# 02_FPGA_Interface.net
KiCad netlist of a schematic drawn in Altium Designer
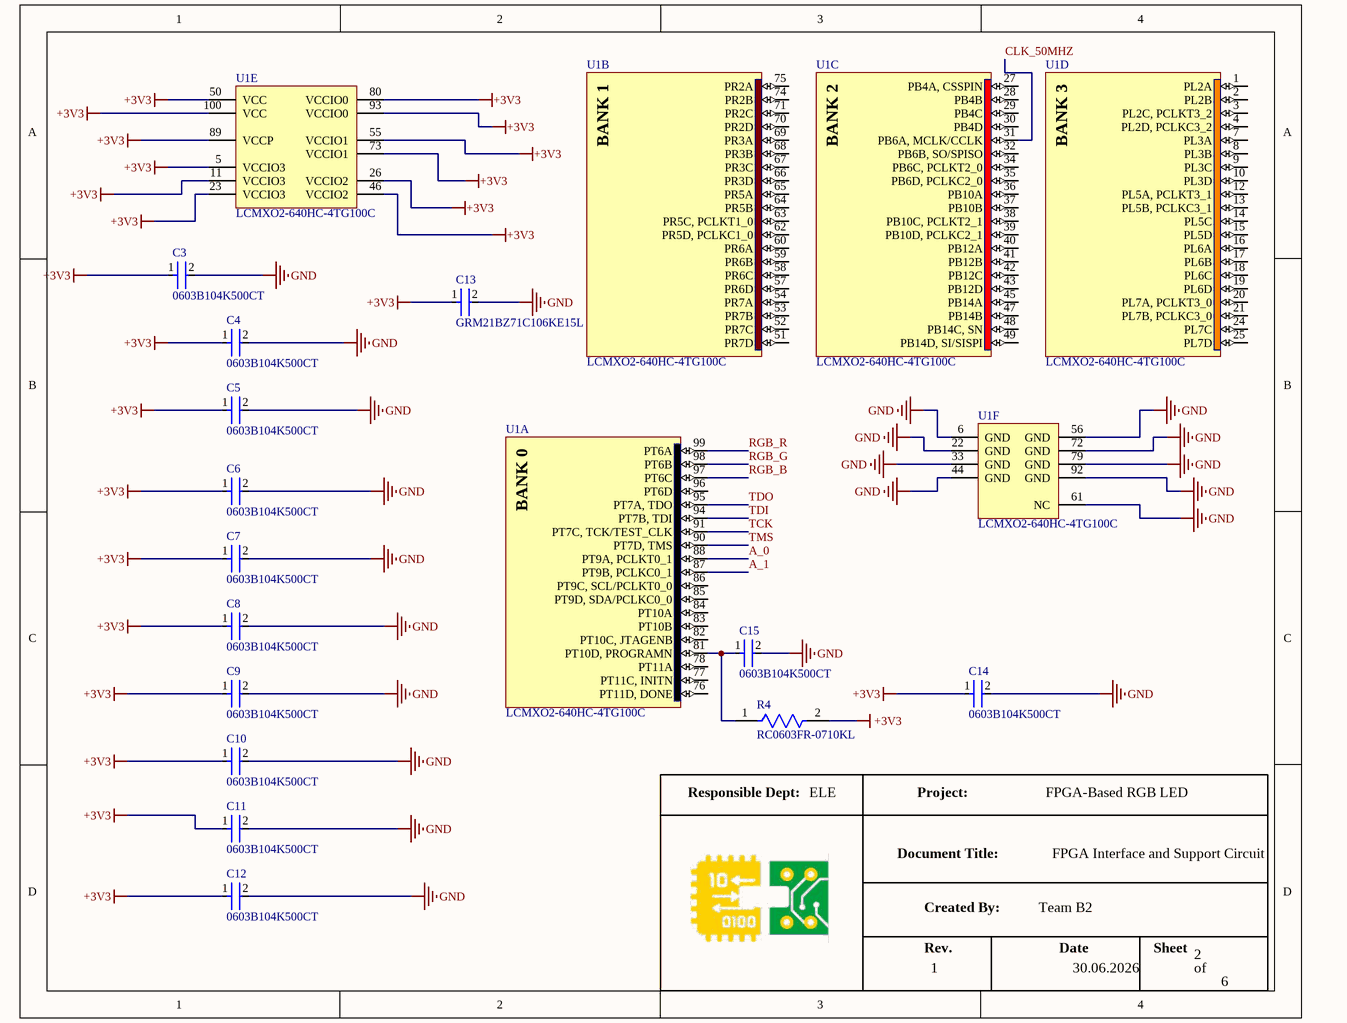
[diagram p0: 02_FPGA_Interface.SchDoc]

(export (version "E")
  (design (tool "Eeschema 10.0.6"))
  (components
    (comp (ref "C3")
      (value "0603B104K500CT")
      (footprint "FP-0603B104K500CT-IPC_C")
      (description "CAP CER 0.1UF 50V X7R 0603")
      (fields (field (name "TOLERANCE") "10%"))
      (libsource (lib "Altium Content Vault") (part "02cd4be3c70576c341d710602a673aa"))
    )
    (comp (ref "C4")
      (value "0603B104K500CT")
      (footprint "FP-0603B104K500CT-IPC_C")
      (description "CAP CER 0.1UF 50V X7R 0603")
      (fields (field (name "TOLERANCE") "10%"))
      (libsource (lib "Altium Content Vault") (part "02cd4be3c70576c341d710602a673aa"))
    )
    (comp (ref "C5")
      (value "0603B104K500CT")
      (footprint "FP-0603B104K500CT-IPC_C")
      (description "CAP CER 0.1UF 50V X7R 0603")
      (fields (field (name "TOLERANCE") "10%"))
      (libsource (lib "Altium Content Vault") (part "02cd4be3c70576c341d710602a673aa"))
    )
    (comp (ref "C6")
      (value "0603B104K500CT")
      (footprint "FP-0603B104K500CT-IPC_C")
      (description "CAP CER 0.1UF 50V X7R 0603")
      (fields (field (name "TOLERANCE") "10%"))
      (libsource (lib "Altium Content Vault") (part "02cd4be3c70576c341d710602a673aa"))
    )
    (comp (ref "C7")
      (value "0603B104K500CT")
      (footprint "FP-0603B104K500CT-IPC_C")
      (description "CAP CER 0.1UF 50V X7R 0603")
      (fields (field (name "TOLERANCE") "10%"))
      (libsource (lib "Altium Content Vault") (part "02cd4be3c70576c341d710602a673aa"))
    )
    (comp (ref "C8")
      (value "0603B104K500CT")
      (footprint "FP-0603B104K500CT-IPC_C")
      (description "CAP CER 0.1UF 50V X7R 0603")
      (fields (field (name "TOLERANCE") "10%"))
      (libsource (lib "Altium Content Vault") (part "02cd4be3c70576c341d710602a673aa"))
    )
    (comp (ref "C9")
      (value "0603B104K500CT")
      (footprint "FP-0603B104K500CT-IPC_C")
      (description "CAP CER 0.1UF 50V X7R 0603")
      (fields (field (name "TOLERANCE") "10%"))
      (libsource (lib "Altium Content Vault") (part "02cd4be3c70576c341d710602a673aa"))
    )
    (comp (ref "C10")
      (value "0603B104K500CT")
      (footprint "FP-0603B104K500CT-IPC_C")
      (description "CAP CER 0.1UF 50V X7R 0603")
      (fields (field (name "TOLERANCE") "10%"))
      (libsource (lib "Altium Content Vault") (part "02cd4be3c70576c341d710602a673aa"))
    )
    (comp (ref "C11")
      (value "0603B104K500CT")
      (footprint "FP-0603B104K500CT-IPC_C")
      (description "CAP CER 0.1UF 50V X7R 0603")
      (fields (field (name "TOLERANCE") "10%"))
      (libsource (lib "Altium Content Vault") (part "02cd4be3c70576c341d710602a673aa"))
    )
    (comp (ref "C12")
      (value "0603B104K500CT")
      (footprint "FP-0603B104K500CT-IPC_C")
      (description "CAP CER 0.1UF 50V X7R 0603")
      (fields (field (name "TOLERANCE") "10%"))
      (libsource (lib "Altium Content Vault") (part "02cd4be3c70576c341d710602a673aa"))
    )
    (comp (ref "C13")
      (value "GRM21BZ71C106KE15L")
      (footprint "FP-GRM21B-0_2-e0_2_0_7-IPC_C")
      (description "Chip Multilayer Ceramic Capacitors for General Purpose, 0805, 10uF, X7R, 15%, 10%, 16V")
      (libsource (lib "Altium Content Vault") (part "b4654b650e69147ec39a6b967a45e02"))
    )
    (comp (ref "C14")
      (value "0603B104K500CT")
      (footprint "FP-0603B104K500CT-IPC_C")
      (description "CAP CER 0.1UF 50V X7R 0603")
      (fields (field (name "TOLERANCE") "10%"))
      (libsource (lib "Altium Content Vault") (part "02cd4be3c70576c341d710602a673aa"))
    )
    (comp (ref "C15")
      (value "0603B104K500CT")
      (footprint "FP-0603B104K500CT-IPC_C")
      (description "CAP CER 0.1UF 50V X7R 0603")
      (fields (field (name "TOLERANCE") "10%"))
      (libsource (lib "Altium Content Vault") (part "02cd4be3c70576c341d710602a673aa"))
    )
    (comp (ref "R4")
      (value "RC0603FR-0710KL")
      (footprint "FP-RC0603-0_55-IPC_C")
      (description "RES 10K OHM 1% 1/10W 0603")
      (fields (field (name "TOLERANCE") "1%"))
      (libsource (lib "Altium Content Vault") (part "1029c3af85768c4190bb7ad29bc67b5"))
    )
    (comp (ref "U1")
      (value "LCMXO2-640HC-4TG100C")
      (footprint "TQFP100_M")
      (libsource (lib "Altium Content Vault") (part "PLD-LTMXO2-640-TQ100"))
    )
  )
  (nets
    (net (code "1") (name "+3V3") (class "Default")
      (node (ref "C10") (pin "1") (pinfunction "1_1") (pintype "passive"))
      (node (ref "C11") (pin "1") (pinfunction "1_1") (pintype "passive"))
      (node (ref "C12") (pin "1") (pinfunction "1_1") (pintype "passive"))
      (node (ref "C13") (pin "1") (pinfunction "1_1") (pintype "passive"))
      (node (ref "C14") (pin "1") (pinfunction "1_1") (pintype "passive"))
      (node (ref "C3") (pin "1") (pinfunction "1_1") (pintype "passive"))
      (node (ref "C4") (pin "1") (pinfunction "1_1") (pintype "passive"))
      (node (ref "C5") (pin "1") (pinfunction "1_1") (pintype "passive"))
      (node (ref "C6") (pin "1") (pinfunction "1_1") (pintype "passive"))
      (node (ref "C7") (pin "1") (pinfunction "1_1") (pintype "passive"))
      (node (ref "C8") (pin "1") (pinfunction "1_1") (pintype "passive"))
      (node (ref "C9") (pin "1") (pinfunction "1_1") (pintype "passive"))
      (node (ref "R4") (pin "2") (pinfunction "2_2") (pintype "passive"))
      (node (ref "U1") (pin "100") (pinfunction "VCC_100") (pintype "power_in"))
      (node (ref "U1") (pin "11") (pinfunction "VCCIO3_11") (pintype "power_in"))
      (node (ref "U1") (pin "23") (pinfunction "VCCIO3_23") (pintype "power_in"))
      (node (ref "U1") (pin "26") (pinfunction "VCCIO2_26") (pintype "power_in"))
      (node (ref "U1") (pin "46") (pinfunction "VCCIO2_46") (pintype "power_in"))
      (node (ref "U1") (pin "5") (pinfunction "VCCIO3_5") (pintype "power_in"))
      (node (ref "U1") (pin "50") (pinfunction "VCC_50") (pintype "power_in"))
      (node (ref "U1") (pin "55") (pinfunction "VCCIO1_55") (pintype "power_in"))
      (node (ref "U1") (pin "73") (pinfunction "VCCIO1_73") (pintype "power_in"))
      (node (ref "U1") (pin "80") (pinfunction "VCCIO0_80") (pintype "power_in"))
      (node (ref "U1") (pin "89") (pinfunction "VCCP_89") (pintype "power_in"))
      (node (ref "U1") (pin "93") (pinfunction "VCCIO0_93") (pintype "power_in"))
    )
    (net (code "2") (name "/A_0") (class "Default")
      (node (ref "U1") (pin "88") (pinfunction "PT9A,_PCLKT0_1_88") (pintype "bidirectional"))
    )
    (net (code "3") (name "/A_1") (class "Default")
      (node (ref "U1") (pin "87") (pinfunction "PT9B,_PCLKC0_1_87") (pintype "bidirectional"))
    )
    (net (code "4") (name "/CLK_50MHZ") (class "Default")
      (node (ref "U1") (pin "31") (pinfunction "PB6A,_MCLK/CCLK_31") (pintype "bidirectional"))
    )
    (net (code "5") (name "/RGB_B") (class "Default")
      (node (ref "U1") (pin "97") (pinfunction "PT6C_97") (pintype "bidirectional"))
    )
    (net (code "6") (name "/RGB_G") (class "Default")
      (node (ref "U1") (pin "98") (pinfunction "PT6B_98") (pintype "bidirectional"))
    )
    (net (code "7") (name "/RGB_R") (class "Default")
      (node (ref "U1") (pin "99") (pinfunction "PT6A_99") (pintype "bidirectional"))
    )
    (net (code "8") (name "/TCK") (class "Default")
      (node (ref "U1") (pin "91") (pinfunction "PT7C,_TCK/TEST_CLK_91") (pintype "bidirectional"))
    )
    (net (code "9") (name "/TDI") (class "Default")
      (node (ref "U1") (pin "94") (pinfunction "PT7B,_TDI_94") (pintype "bidirectional"))
    )
    (net (code "10") (name "/TDO") (class "Default")
      (node (ref "U1") (pin "95") (pinfunction "PT7A,_TDO_95") (pintype "bidirectional"))
    )
    (net (code "11") (name "/TMS") (class "Default")
      (node (ref "U1") (pin "90") (pinfunction "PT7D,_TMS_90") (pintype "bidirectional"))
    )
    (net (code "12") (name "GND") (class "Default")
      (node (ref "C10") (pin "2") (pinfunction "2_2") (pintype "passive"))
      (node (ref "C11") (pin "2") (pinfunction "2_2") (pintype "passive"))
      (node (ref "C12") (pin "2") (pinfunction "2_2") (pintype "passive"))
      (node (ref "C13") (pin "2") (pinfunction "2_2") (pintype "passive"))
      (node (ref "C14") (pin "2") (pinfunction "2_2") (pintype "passive"))
      (node (ref "C15") (pin "2") (pinfunction "2_2") (pintype "passive"))
      (node (ref "C3") (pin "2") (pinfunction "2_2") (pintype "passive"))
      (node (ref "C4") (pin "2") (pinfunction "2_2") (pintype "passive"))
      (node (ref "C5") (pin "2") (pinfunction "2_2") (pintype "passive"))
      (node (ref "C6") (pin "2") (pinfunction "2_2") (pintype "passive"))
      (node (ref "C7") (pin "2") (pinfunction "2_2") (pintype "passive"))
      (node (ref "C8") (pin "2") (pinfunction "2_2") (pintype "passive"))
      (node (ref "C9") (pin "2") (pinfunction "2_2") (pintype "passive"))
      (node (ref "U1") (pin "22") (pinfunction "GND_22") (pintype "power_in"))
      (node (ref "U1") (pin "33") (pinfunction "GND_33") (pintype "power_in"))
      (node (ref "U1") (pin "44") (pinfunction "GND_44") (pintype "power_in"))
      (node (ref "U1") (pin "56") (pinfunction "GND_56") (pintype "power_in"))
      (node (ref "U1") (pin "6") (pinfunction "GND_6") (pintype "power_in"))
      (node (ref "U1") (pin "61") (pinfunction "NC_61") (pintype "passive"))
      (node (ref "U1") (pin "72") (pinfunction "GND_72") (pintype "power_in"))
      (node (ref "U1") (pin "79") (pinfunction "GND_79") (pintype "power_in"))
      (node (ref "U1") (pin "92") (pinfunction "GND_92") (pintype "power_in"))
    )
    (net (code "13") (name "Net-(U1A-PT10D,_PROGRAMN)") (class "Default")
      (node (ref "C15") (pin "1") (pinfunction "1_1") (pintype "passive"))
      (node (ref "R4") (pin "1") (pinfunction "1_1") (pintype "passive"))
      (node (ref "U1") (pin "81") (pinfunction "PT10D,_PROGRAMN_81") (pintype "bidirectional"))
    )
    (net (code "14") (name "unconnected-(U1A-PT6D-Pad96)") (class "Default")
      (node (ref "U1") (pin "96") (pinfunction "PT6D_96") (pintype "bidirectional"))
    )
    (net (code "15") (name "unconnected-(U1A-PT9C,_SCL{slash}PCLKT0_0-Pad86)") (class "Default")
      (node (ref "U1") (pin "86") (pinfunction "PT9C,_SCL/PCLKT0_0_86") (pintype "bidirectional"))
    )
    (net (code "16") (name "unconnected-(U1A-PT9D,_SDA{slash}PCLKC0_0-Pad85)") (class "Default")
      (node (ref "U1") (pin "85") (pinfunction "PT9D,_SDA/PCLKC0_0_85") (pintype "bidirectional"))
    )
    (net (code "17") (name "unconnected-(U1A-PT10A-Pad84)") (class "Default")
      (node (ref "U1") (pin "84") (pinfunction "PT10A_84") (pintype "bidirectional"))
    )
    (net (code "18") (name "unconnected-(U1A-PT10B-Pad83)") (class "Default")
      (node (ref "U1") (pin "83") (pinfunction "PT10B_83") (pintype "bidirectional"))
    )
    (net (code "19") (name "unconnected-(U1A-PT10C,_JTAGENB-Pad82)") (class "Default")
      (node (ref "U1") (pin "82") (pinfunction "PT10C,_JTAGENB_82") (pintype "bidirectional"))
    )
    (net (code "20") (name "unconnected-(U1A-PT11A-Pad78)") (class "Default")
      (node (ref "U1") (pin "78") (pinfunction "PT11A_78") (pintype "bidirectional"))
    )
    (net (code "21") (name "unconnected-(U1A-PT11C,_INITN-Pad77)") (class "Default")
      (node (ref "U1") (pin "77") (pinfunction "PT11C,_INITN_77") (pintype "bidirectional"))
    )
    (net (code "22") (name "unconnected-(U1A-PT11D,_DONE-Pad76)") (class "Default")
      (node (ref "U1") (pin "76") (pinfunction "PT11D,_DONE_76") (pintype "bidirectional"))
    )
    (net (code "23") (name "unconnected-(U1B-PR2A-Pad75)") (class "Default")
      (node (ref "U1") (pin "75") (pinfunction "PR2A_75") (pintype "bidirectional"))
    )
    (net (code "24") (name "unconnected-(U1B-PR2B-Pad74)") (class "Default")
      (node (ref "U1") (pin "74") (pinfunction "PR2B_74") (pintype "bidirectional"))
    )
    (net (code "25") (name "unconnected-(U1B-PR2C-Pad71)") (class "Default")
      (node (ref "U1") (pin "71") (pinfunction "PR2C_71") (pintype "bidirectional"))
    )
    (net (code "26") (name "unconnected-(U1B-PR2D-Pad70)") (class "Default")
      (node (ref "U1") (pin "70") (pinfunction "PR2D_70") (pintype "bidirectional"))
    )
    (net (code "27") (name "unconnected-(U1B-PR3A-Pad69)") (class "Default")
      (node (ref "U1") (pin "69") (pinfunction "PR3A_69") (pintype "bidirectional"))
    )
    (net (code "28") (name "unconnected-(U1B-PR3B-Pad68)") (class "Default")
      (node (ref "U1") (pin "68") (pinfunction "PR3B_68") (pintype "bidirectional"))
    )
    (net (code "29") (name "unconnected-(U1B-PR3C-Pad67)") (class "Default")
      (node (ref "U1") (pin "67") (pinfunction "PR3C_67") (pintype "bidirectional"))
    )
    (net (code "30") (name "unconnected-(U1B-PR3D-Pad66)") (class "Default")
      (node (ref "U1") (pin "66") (pinfunction "PR3D_66") (pintype "bidirectional"))
    )
    (net (code "31") (name "unconnected-(U1B-PR5A-Pad65)") (class "Default")
      (node (ref "U1") (pin "65") (pinfunction "PR5A_65") (pintype "bidirectional"))
    )
    (net (code "32") (name "unconnected-(U1B-PR5B-Pad64)") (class "Default")
      (node (ref "U1") (pin "64") (pinfunction "PR5B_64") (pintype "bidirectional"))
    )
    (net (code "33") (name "unconnected-(U1B-PR5C,_PCLKT1_0-Pad63)") (class "Default")
      (node (ref "U1") (pin "63") (pinfunction "PR5C,_PCLKT1_0_63") (pintype "bidirectional"))
    )
    (net (code "34") (name "unconnected-(U1B-PR5D,_PCLKC1_0-Pad62)") (class "Default")
      (node (ref "U1") (pin "62") (pinfunction "PR5D,_PCLKC1_0_62") (pintype "bidirectional"))
    )
    (net (code "35") (name "unconnected-(U1B-PR6A-Pad60)") (class "Default")
      (node (ref "U1") (pin "60") (pinfunction "PR6A_60") (pintype "bidirectional"))
    )
    (net (code "36") (name "unconnected-(U1B-PR6B-Pad59)") (class "Default")
      (node (ref "U1") (pin "59") (pinfunction "PR6B_59") (pintype "bidirectional"))
    )
    (net (code "37") (name "unconnected-(U1B-PR6C-Pad58)") (class "Default")
      (node (ref "U1") (pin "58") (pinfunction "PR6C_58") (pintype "bidirectional"))
    )
    (net (code "38") (name "unconnected-(U1B-PR6D-Pad57)") (class "Default")
      (node (ref "U1") (pin "57") (pinfunction "PR6D_57") (pintype "bidirectional"))
    )
    (net (code "39") (name "unconnected-(U1B-PR7A-Pad54)") (class "Default")
      (node (ref "U1") (pin "54") (pinfunction "PR7A_54") (pintype "bidirectional"))
    )
    (net (code "40") (name "unconnected-(U1B-PR7B-Pad53)") (class "Default")
      (node (ref "U1") (pin "53") (pinfunction "PR7B_53") (pintype "bidirectional"))
    )
    (net (code "41") (name "unconnected-(U1B-PR7C-Pad52)") (class "Default")
      (node (ref "U1") (pin "52") (pinfunction "PR7C_52") (pintype "bidirectional"))
    )
    (net (code "42") (name "unconnected-(U1B-PR7D-Pad51)") (class "Default")
      (node (ref "U1") (pin "51") (pinfunction "PR7D_51") (pintype "bidirectional"))
    )
    (net (code "43") (name "unconnected-(U1C-PB4A,_CSSPIN-Pad27)") (class "Default")
      (node (ref "U1") (pin "27") (pinfunction "PB4A,_CSSPIN_27") (pintype "bidirectional"))
    )
    (net (code "44") (name "unconnected-(U1C-PB4B-Pad28)") (class "Default")
      (node (ref "U1") (pin "28") (pinfunction "PB4B_28") (pintype "bidirectional"))
    )
    (net (code "45") (name "unconnected-(U1C-PB4C-Pad29)") (class "Default")
      (node (ref "U1") (pin "29") (pinfunction "PB4C_29") (pintype "bidirectional"))
    )
    (net (code "46") (name "unconnected-(U1C-PB4D-Pad30)") (class "Default")
      (node (ref "U1") (pin "30") (pinfunction "PB4D_30") (pintype "bidirectional"))
    )
    (net (code "47") (name "unconnected-(U1C-PB6B,_SO{slash}SPISO-Pad32)") (class "Default")
      (node (ref "U1") (pin "32") (pinfunction "PB6B,_SO/SPISO_32") (pintype "bidirectional"))
    )
    (net (code "48") (name "unconnected-(U1C-PB6C,_PCLKT2_0-Pad34)") (class "Default")
      (node (ref "U1") (pin "34") (pinfunction "PB6C,_PCLKT2_0_34") (pintype "bidirectional"))
    )
    (net (code "49") (name "unconnected-(U1C-PB6D,_PCLKC2_0-Pad35)") (class "Default")
      (node (ref "U1") (pin "35") (pinfunction "PB6D,_PCLKC2_0_35") (pintype "bidirectional"))
    )
    (net (code "50") (name "unconnected-(U1C-PB10A-Pad36)") (class "Default")
      (node (ref "U1") (pin "36") (pinfunction "PB10A_36") (pintype "bidirectional"))
    )
    (net (code "51") (name "unconnected-(U1C-PB10B-Pad37)") (class "Default")
      (node (ref "U1") (pin "37") (pinfunction "PB10B_37") (pintype "bidirectional"))
    )
    (net (code "52") (name "unconnected-(U1C-PB10C,_PCLKT2_1-Pad38)") (class "Default")
      (node (ref "U1") (pin "38") (pinfunction "PB10C,_PCLKT2_1_38") (pintype "bidirectional"))
    )
    (net (code "53") (name "unconnected-(U1C-PB10D,_PCLKC2_1-Pad39)") (class "Default")
      (node (ref "U1") (pin "39") (pinfunction "PB10D,_PCLKC2_1_39") (pintype "bidirectional"))
    )
    (net (code "54") (name "unconnected-(U1C-PB12A-Pad40)") (class "Default")
      (node (ref "U1") (pin "40") (pinfunction "PB12A_40") (pintype "bidirectional"))
    )
    (net (code "55") (name "unconnected-(U1C-PB12B-Pad41)") (class "Default")
      (node (ref "U1") (pin "41") (pinfunction "PB12B_41") (pintype "bidirectional"))
    )
    (net (code "56") (name "unconnected-(U1C-PB12C-Pad42)") (class "Default")
      (node (ref "U1") (pin "42") (pinfunction "PB12C_42") (pintype "bidirectional"))
    )
    (net (code "57") (name "unconnected-(U1C-PB12D-Pad43)") (class "Default")
      (node (ref "U1") (pin "43") (pinfunction "PB12D_43") (pintype "bidirectional"))
    )
    (net (code "58") (name "unconnected-(U1C-PB14A-Pad45)") (class "Default")
      (node (ref "U1") (pin "45") (pinfunction "PB14A_45") (pintype "bidirectional"))
    )
    (net (code "59") (name "unconnected-(U1C-PB14B-Pad47)") (class "Default")
      (node (ref "U1") (pin "47") (pinfunction "PB14B_47") (pintype "bidirectional"))
    )
    (net (code "60") (name "unconnected-(U1C-PB14C,_SN-Pad48)") (class "Default")
      (node (ref "U1") (pin "48") (pinfunction "PB14C,_SN_48") (pintype "bidirectional"))
    )
    (net (code "61") (name "unconnected-(U1C-PB14D,_SI{slash}SISPI-Pad49)") (class "Default")
      (node (ref "U1") (pin "49") (pinfunction "PB14D,_SI/SISPI_49") (pintype "bidirectional"))
    )
    (net (code "62") (name "unconnected-(U1D-PL2A-Pad1)") (class "Default")
      (node (ref "U1") (pin "1") (pinfunction "PL2A_1") (pintype "bidirectional"))
    )
    (net (code "63") (name "unconnected-(U1D-PL2B-Pad2)") (class "Default")
      (node (ref "U1") (pin "2") (pinfunction "PL2B_2") (pintype "bidirectional"))
    )
    (net (code "64") (name "unconnected-(U1D-PL2C,_PCLKT3_2-Pad3)") (class "Default")
      (node (ref "U1") (pin "3") (pinfunction "PL2C,_PCLKT3_2_3") (pintype "bidirectional"))
    )
    (net (code "65") (name "unconnected-(U1D-PL2D,_PCLKC3_2-Pad4)") (class "Default")
      (node (ref "U1") (pin "4") (pinfunction "PL2D,_PCLKC3_2_4") (pintype "bidirectional"))
    )
    (net (code "66") (name "unconnected-(U1D-PL3A-Pad7)") (class "Default")
      (node (ref "U1") (pin "7") (pinfunction "PL3A_7") (pintype "bidirectional"))
    )
    (net (code "67") (name "unconnected-(U1D-PL3B-Pad8)") (class "Default")
      (node (ref "U1") (pin "8") (pinfunction "PL3B_8") (pintype "bidirectional"))
    )
    (net (code "68") (name "unconnected-(U1D-PL3C-Pad9)") (class "Default")
      (node (ref "U1") (pin "9") (pinfunction "PL3C_9") (pintype "bidirectional"))
    )
    (net (code "69") (name "unconnected-(U1D-PL3D-Pad10)") (class "Default")
      (node (ref "U1") (pin "10") (pinfunction "PL3D_10") (pintype "bidirectional"))
    )
    (net (code "70") (name "unconnected-(U1D-PL5A,_PCLKT3_1-Pad12)") (class "Default")
      (node (ref "U1") (pin "12") (pinfunction "PL5A,_PCLKT3_1_12") (pintype "bidirectional"))
    )
    (net (code "71") (name "unconnected-(U1D-PL5B,_PCLKC3_1-Pad13)") (class "Default")
      (node (ref "U1") (pin "13") (pinfunction "PL5B,_PCLKC3_1_13") (pintype "bidirectional"))
    )
    (net (code "72") (name "unconnected-(U1D-PL5C-Pad14)") (class "Default")
      (node (ref "U1") (pin "14") (pinfunction "PL5C_14") (pintype "bidirectional"))
    )
    (net (code "73") (name "unconnected-(U1D-PL5D-Pad15)") (class "Default")
      (node (ref "U1") (pin "15") (pinfunction "PL5D_15") (pintype "bidirectional"))
    )
    (net (code "74") (name "unconnected-(U1D-PL6A-Pad16)") (class "Default")
      (node (ref "U1") (pin "16") (pinfunction "PL6A_16") (pintype "bidirectional"))
    )
    (net (code "75") (name "unconnected-(U1D-PL6B-Pad17)") (class "Default")
      (node (ref "U1") (pin "17") (pinfunction "PL6B_17") (pintype "bidirectional"))
    )
    (net (code "76") (name "unconnected-(U1D-PL6C-Pad18)") (class "Default")
      (node (ref "U1") (pin "18") (pinfunction "PL6C_18") (pintype "bidirectional"))
    )
    (net (code "77") (name "unconnected-(U1D-PL6D-Pad19)") (class "Default")
      (node (ref "U1") (pin "19") (pinfunction "PL6D_19") (pintype "bidirectional"))
    )
    (net (code "78") (name "unconnected-(U1D-PL7A,_PCLKT3_0-Pad20)") (class "Default")
      (node (ref "U1") (pin "20") (pinfunction "PL7A,_PCLKT3_0_20") (pintype "bidirectional"))
    )
    (net (code "79") (name "unconnected-(U1D-PL7B,_PCLKC3_0-Pad21)") (class "Default")
      (node (ref "U1") (pin "21") (pinfunction "PL7B,_PCLKC3_0_21") (pintype "bidirectional"))
    )
    (net (code "80") (name "unconnected-(U1D-PL7C-Pad24)") (class "Default")
      (node (ref "U1") (pin "24") (pinfunction "PL7C_24") (pintype "bidirectional"))
    )
    (net (code "81") (name "unconnected-(U1D-PL7D-Pad25)") (class "Default")
      (node (ref "U1") (pin "25") (pinfunction "PL7D_25") (pintype "bidirectional"))
    )
  )
)
